# obc_imu.net
KiCad netlist of a schematic drawn in Altium Designer
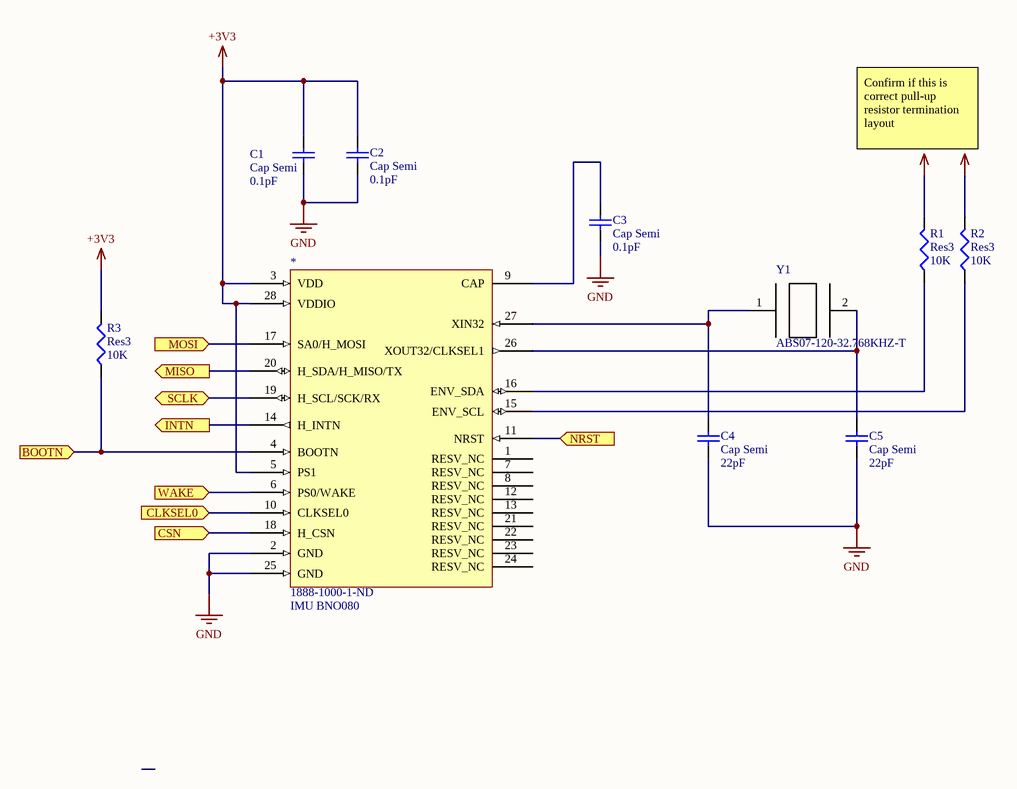
[diagram p0: obc_imu.SchDoc]

(export (version "E")
  (design (tool "Eeschema 10.0.6"))
  (components
    (comp (ref "*")
      (value "IMU BNO080")
      (footprint "LGA-28")
      (description "ACCEL/GYRO/MAG I2C 32BIT")
      (libsource (lib "ICs") (part "IMU BNO080"))
    )
    (comp (ref "C1")
      (value "Cap Semi")
      (footprint "1608[0603]")
      (description "Capacitor (Semiconductor SIM Model)")
      (fields (field (name "ALTIUM_VALUE") "0.1pF") (field (name "PUBLISHER") "Altium Limited"))
      (libsource (lib "Miscellaneous Devices") (part "Cap Semi"))
    )
    (comp (ref "C2")
      (value "Cap Semi")
      (footprint "1608[0603]")
      (description "Capacitor (Semiconductor SIM Model)")
      (fields (field (name "ALTIUM_VALUE") "0.1pF") (field (name "PUBLISHER") "Altium Limited"))
      (libsource (lib "Miscellaneous Devices") (part "Cap Semi"))
    )
    (comp (ref "C3")
      (value "Cap Semi")
      (footprint "1608[0603]")
      (description "Capacitor (Semiconductor SIM Model)")
      (fields (field (name "ALTIUM_VALUE") "0.1pF") (field (name "PUBLISHER") "Altium Limited"))
      (libsource (lib "Miscellaneous Devices") (part "Cap Semi"))
    )
    (comp (ref "C4")
      (value "Cap Semi")
      (footprint "1608[0603]")
      (description "Capacitor (Semiconductor SIM Model)")
      (fields (field (name "ALTIUM_VALUE") "22pF") (field (name "PUBLISHER") "Altium Limited"))
      (libsource (lib "Miscellaneous Devices") (part "Cap Semi"))
    )
    (comp (ref "C5")
      (value "Cap Semi")
      (footprint "1608[0603]")
      (description "Capacitor (Semiconductor SIM Model)")
      (fields (field (name "ALTIUM_VALUE") "22pF") (field (name "PUBLISHER") "Altium Limited"))
      (libsource (lib "Miscellaneous Devices") (part "Cap Semi"))
    )
    (comp (ref "R1")
      (value "Res3")
      (footprint "J1-0603")
      (description "Resistor")
      (fields (field (name "ALTIUM_VALUE") "10K") (field (name "PUBLISHER") "Altium Limited"))
      (libsource (lib "Miscellaneous Devices") (part "Res3"))
    )
    (comp (ref "R2")
      (value "Res3")
      (footprint "J1-0603")
      (description "Resistor")
      (fields (field (name "ALTIUM_VALUE") "10K") (field (name "PUBLISHER") "Altium Limited"))
      (libsource (lib "Miscellaneous Devices") (part "Res3"))
    )
    (comp (ref "R3")
      (value "Res3")
      (footprint "J1-0603")
      (description "Resistor")
      (fields (field (name "ALTIUM_VALUE") "10K") (field (name "PUBLISHER") "Altium Limited"))
      (libsource (lib "Miscellaneous Devices") (part "Res3"))
    )
    (comp (ref "Y1")
      (value "ABS07-120-32.768KHZ-T")
      (footprint "XTAL_ABS07-120-32.768KHZ-T")
      (fields (field (name "MF") "Abracon"))
      (libsource (lib "ABS07-120-32.768KHZ-T") (part "ABS07-120-32.768KHZ-T"))
    )
  )
  (nets
    (net (code "1") (name "+3V3") (class "Default")
      (node (ref "*") (pin "28") (pinfunction "VDDIO_28") (pintype "input"))
      (node (ref "*") (pin "3") (pinfunction "VDD_3") (pintype "input"))
      (node (ref "*") (pin "5") (pinfunction "PS1_5") (pintype "input"))
      (node (ref "C1") (pin "2") (pinfunction "2_2") (pintype "passive"))
      (node (ref "C2") (pin "2") (pinfunction "2_2") (pintype "passive"))
      (node (ref "R1") (pin "2") (pinfunction "2_2") (pintype "passive"))
      (node (ref "R2") (pin "2") (pinfunction "2_2") (pintype "passive"))
      (node (ref "R3") (pin "2") (pinfunction "2_2") (pintype "passive"))
    )
    (net (code "2") (name "/BOOTN") (class "Default")
      (node (ref "*") (pin "4") (pinfunction "BOOTN_4") (pintype "input"))
      (node (ref "R3") (pin "1") (pinfunction "1_1") (pintype "passive"))
    )
    (net (code "3") (name "/CLKSEL0") (class "Default")
      (node (ref "*") (pin "10") (pinfunction "CLKSEL0_10") (pintype "input"))
    )
    (net (code "4") (name "/CSN") (class "Default")
      (node (ref "*") (pin "18") (pinfunction "H_CSN_18") (pintype "input"))
    )
    (net (code "5") (name "/INTN") (class "Default")
      (node (ref "*") (pin "14") (pinfunction "H_INTN_14") (pintype "output"))
    )
    (net (code "6") (name "/MISO") (class "Default")
      (node (ref "*") (pin "20") (pinfunction "H_SDA/H_MISO/TX_20") (pintype "bidirectional"))
    )
    (net (code "7") (name "/MOSI") (class "Default")
      (node (ref "*") (pin "17") (pinfunction "SA0/H_MOSI_17") (pintype "input"))
    )
    (net (code "8") (name "/NRST") (class "Default")
      (node (ref "*") (pin "11") (pinfunction "NRST_11") (pintype "input"))
    )
    (net (code "9") (name "/SCLK") (class "Default")
      (node (ref "*") (pin "19") (pinfunction "H_SCL/SCK/RX_19") (pintype "bidirectional"))
    )
    (net (code "10") (name "/WAKE") (class "Default")
      (node (ref "*") (pin "6") (pinfunction "PS0/WAKE_6") (pintype "input"))
    )
    (net (code "11") (name "GND") (class "Default")
      (node (ref "*") (pin "2") (pinfunction "GND_2") (pintype "input"))
      (node (ref "*") (pin "25") (pinfunction "GND_25") (pintype "input"))
      (node (ref "C1") (pin "1") (pinfunction "1_1") (pintype "passive"))
      (node (ref "C2") (pin "1") (pinfunction "1_1") (pintype "passive"))
      (node (ref "C3") (pin "1") (pinfunction "1_1") (pintype "passive"))
      (node (ref "C4") (pin "1") (pinfunction "1_1") (pintype "passive"))
      (node (ref "C5") (pin "1") (pinfunction "1_1") (pintype "passive"))
    )
    (net (code "12") (name "Net-(*-CAP)") (class "Default")
      (node (ref "*") (pin "9") (pinfunction "CAP_9") (pintype "passive"))
      (node (ref "C3") (pin "2") (pinfunction "2_2") (pintype "passive"))
    )
    (net (code "13") (name "Net-(*-ENV_SCL)") (class "Default")
      (node (ref "*") (pin "15") (pinfunction "ENV_SCL_15") (pintype "bidirectional"))
      (node (ref "R2") (pin "1") (pinfunction "1_1") (pintype "passive"))
    )
    (net (code "14") (name "Net-(*-ENV_SDA)") (class "Default")
      (node (ref "*") (pin "16") (pinfunction "ENV_SDA_16") (pintype "bidirectional"))
      (node (ref "R1") (pin "1") (pinfunction "1_1") (pintype "passive"))
    )
    (net (code "15") (name "Net-(*-XIN32)") (class "Default")
      (node (ref "*") (pin "27") (pinfunction "XIN32_27") (pintype "input"))
      (node (ref "C4") (pin "2") (pinfunction "2_2") (pintype "passive"))
      (node (ref "Y1") (pin "1") (pinfunction "1_1") (pintype "passive"))
    )
    (net (code "16") (name "Net-(*-XOUT32{slash}CLKSEL1)") (class "Default")
      (node (ref "*") (pin "26") (pinfunction "XOUT32/CLKSEL1_26") (pintype "output"))
      (node (ref "C5") (pin "2") (pinfunction "2_2") (pintype "passive"))
      (node (ref "Y1") (pin "2") (pinfunction "2_2") (pintype "passive"))
    )
    (net (code "17") (name "unconnected-(*-RESV_NC-Pad1)") (class "Default")
      (node (ref "*") (pin "1") (pinfunction "RESV_NC_1") (pintype "passive"))
    )
    (net (code "18") (name "unconnected-(*-RESV_NC-Pad7)") (class "Default")
      (node (ref "*") (pin "7") (pinfunction "RESV_NC_7") (pintype "passive"))
    )
    (net (code "19") (name "unconnected-(*-RESV_NC-Pad8)") (class "Default")
      (node (ref "*") (pin "8") (pinfunction "RESV_NC_8") (pintype "passive"))
    )
    (net (code "20") (name "unconnected-(*-RESV_NC-Pad12)") (class "Default")
      (node (ref "*") (pin "12") (pinfunction "RESV_NC_12") (pintype "passive"))
    )
    (net (code "21") (name "unconnected-(*-RESV_NC-Pad13)") (class "Default")
      (node (ref "*") (pin "13") (pinfunction "RESV_NC_13") (pintype "passive"))
    )
    (net (code "22") (name "unconnected-(*-RESV_NC-Pad21)") (class "Default")
      (node (ref "*") (pin "21") (pinfunction "RESV_NC_21") (pintype "passive"))
    )
    (net (code "23") (name "unconnected-(*-RESV_NC-Pad22)") (class "Default")
      (node (ref "*") (pin "22") (pinfunction "RESV_NC_22") (pintype "passive"))
    )
    (net (code "24") (name "unconnected-(*-RESV_NC-Pad23)") (class "Default")
      (node (ref "*") (pin "23") (pinfunction "RESV_NC_23") (pintype "passive"))
    )
    (net (code "25") (name "unconnected-(*-RESV_NC-Pad24)") (class "Default")
      (node (ref "*") (pin "24") (pinfunction "RESV_NC_24") (pintype "passive"))
    )
  )
)
